# 01_Power.net
KiCad netlist of a schematic drawn in Altium Designer
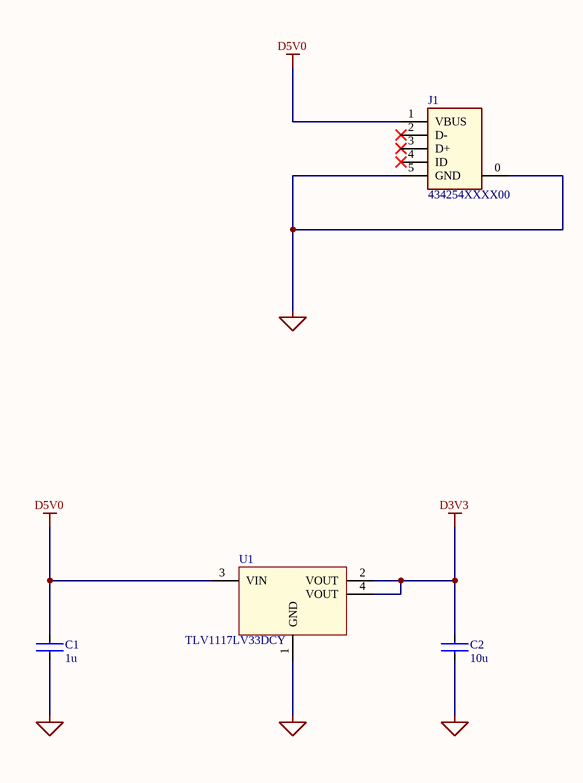
[diagram p0: 01_Power.SchDoc]

(export (version "E")
  (design (tool "Eeschema 10.0.6"))
  (components
    (comp (ref "C1")
      (value "1u")
      (footprint "CAPC1608X09N_C0603")
      (description "CAP,Ceramic,X7R,10%,16V,1uF,0603")
      (libsource (lib "AD15_libpkg") (part "CAP12"))
    )
    (comp (ref "C2")
      (value "10u")
      (footprint "CAPC1608X09N_C0603")
      (description "CAP,Ceramic,X7R,10%,6.3V,10uF,0603")
      (libsource (lib "C0603") (part "CAP113"))
    )
    (comp (ref "J1")
      (value "434254XXXX00")
      (footprint "434254XXXX00")
      (description "Mini-USB Receptacle,5-Pin,0.8mm Pitch,SMD")
      (libsource (lib "AD15_libpkg") (part "434254XXXX00"))
    )
    (comp (ref "U1")
      (value "TLV1117LV33DCY")
      (footprint "SOT230P700X180-4N_SOT223_TLV1117LV")
      (description "IC,LDO,1000mA,3.3V,SOT223")
      (libsource (lib "AD15_libpkg") (part "TLV1117LV33DCY"))
    )
  )
  (nets
    (net (code "1") (name "D3V3") (class "Default")
      (node (ref "C2") (pin "1") (pinfunction "0_1") (pintype "passive"))
      (node (ref "U1") (pin "2") (pinfunction "VOUT_2") (pintype "passive"))
      (node (ref "U1") (pin "4") (pinfunction "VOUT_4") (pintype "passive"))
    )
    (net (code "2") (name "D5V0") (class "Default")
      (node (ref "C1") (pin "1") (pinfunction "0_1") (pintype "passive"))
      (node (ref "J1") (pin "1") (pinfunction "VBUS_1") (pintype "passive"))
      (node (ref "U1") (pin "3") (pinfunction "VIN_3") (pintype "passive"))
    )
    (net (code "3") (name "GND") (class "Default")
      (node (ref "C1") (pin "2") (pinfunction "1_2") (pintype "passive"))
      (node (ref "C2") (pin "2") (pinfunction "1_2") (pintype "passive"))
      (node (ref "J1") (pin "0") (pintype "passive"))
      (node (ref "J1") (pin "5") (pinfunction "GND_5") (pintype "passive"))
      (node (ref "U1") (pin "1") (pinfunction "GND_1") (pintype "passive"))
    )
    (net (code "4") (name "unconnected-(J1-D+-Pad3)") (class "Default")
      (node (ref "J1") (pin "3") (pinfunction "D+_3") (pintype "passive+no_connect"))
    )
    (net (code "5") (name "unconnected-(J1-D--Pad2)") (class "Default")
      (node (ref "J1") (pin "2") (pinfunction "D-_2") (pintype "passive+no_connect"))
    )
    (net (code "6") (name "unconnected-(J1-ID-Pad4)") (class "Default")
      (node (ref "J1") (pin "4") (pinfunction "ID_4") (pintype "passive+no_connect"))
    )
  )
)
